# VISUR-N_a.net
KiCad netlist of a schematic drawn in Altium Designer
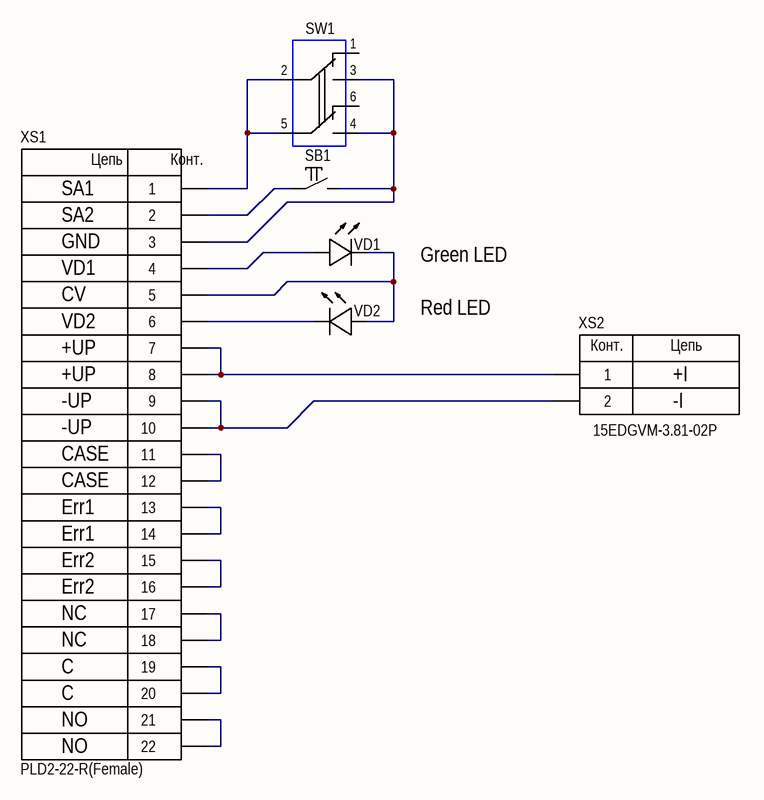
[diagram p0: VISUR-N_a.SchDoc]

(export (version "E")
  (design (tool "Eeschema 10.0.6"))
  (components
    (comp (ref "SB1")
      (value "~")
      (footprint "BUT: 6x6")
      (fields
        (field (name "MANUFACTURER") "TE Connectivity")
        (field (name "VALUEMANUFACTURERPARTNUMBER") "Tactile button, 6x6mm")
        (field (name "PARTNUMBER") "FSM2JSMAATR")
      )
      (libsource (lib "electromechanics") (part "Button_tactile"))
    )
    (comp (ref "SW1")
      (value "JS202011SCQN")
      (footprint "JS202011CQN")
      (description "Переключатель")
      (fields
        (field (name "MANUFACTURER") "C&K Component")
        (field (name "REPLACEMENTPART1PARTNUMBER") "is-1390")
      )
      (libsource (lib "Switch") (part "JS202011SCQN"))
    )
    (comp (ref "VD1")
      (value "KM2520SURCK09")
      (footprint "KM2520SURCK09")
      (description "LED")
      (libsource (lib "Kingbright LED") (part "KM2520SURCK09"))
    )
    (comp (ref "VD2")
      (value "KM2520SURCK09")
      (footprint "KM2520SURCK09")
      (description "LED")
      (libsource (lib "Kingbright LED") (part "KM2520SURCK09"))
    )
    (comp (ref "XS1")
      (value "PLD2-22-R(Female)")
      (footprint "CON: PLD2-22-R(Female)")
      (libsource (lib "connector") (part "PLD2-22(Female)"))
    )
    (comp (ref "XS2")
      (value "15EDGVM-3.81-02P")
      (footprint "CON: 15EDGVM-3.81-02P")
      (libsource (lib "connector") (part "15EDGVM-3.81-02P"))
    )
  )
  (nets
    (net (code "1") (name "Net-(SB1-Pad1)") (class "Default")
      (node (ref "SB1") (pin "1") (pinfunction "1_1") (pintype "passive"))
      (node (ref "XS1") (pin "2") (pinfunction "2_2") (pintype "passive"))
    )
    (net (code "2") (name "Net-(SB1-Pad2)") (class "Default")
      (node (ref "SB1") (pin "2") (pinfunction "2_2") (pintype "passive"))
      (node (ref "SW1") (pin "3") (pinfunction "3_3") (pintype "passive"))
      (node (ref "SW1") (pin "4") (pinfunction "4_4") (pintype "passive"))
      (node (ref "XS1") (pin "3") (pinfunction "3_3") (pintype "power_in"))
    )
    (net (code "3") (name "Net-(SW1-Pad2)") (class "Default")
      (node (ref "SW1") (pin "2") (pinfunction "2_2") (pintype "passive"))
      (node (ref "SW1") (pin "5") (pinfunction "5_5") (pintype "passive"))
      (node (ref "XS1") (pin "1") (pinfunction "1_1") (pintype "passive"))
    )
    (net (code "4") (name "Net-(VD1-A)") (class "Default")
      (node (ref "VD1") (pin "1") (pinfunction "A_1") (pintype "passive"))
      (node (ref "XS1") (pin "4") (pinfunction "4_4") (pintype "power_in"))
    )
    (net (code "5") (name "Net-(VD1-K)") (class "Default")
      (node (ref "VD1") (pin "2") (pinfunction "K_2") (pintype "passive"))
      (node (ref "VD2") (pin "1") (pinfunction "A_1") (pintype "passive"))
      (node (ref "XS1") (pin "5") (pinfunction "5_5") (pintype "power_in"))
    )
    (net (code "6") (name "Net-(VD2-K)") (class "Default")
      (node (ref "VD2") (pin "2") (pinfunction "K_2") (pintype "passive"))
      (node (ref "XS1") (pin "6") (pinfunction "6_6") (pintype "power_in"))
    )
    (net (code "7") (name "Net-(XS1-Pad7)") (class "Default")
      (node (ref "XS1") (pin "7") (pinfunction "7_7") (pintype "power_in"))
      (node (ref "XS1") (pin "8") (pinfunction "8_8") (pintype "power_in"))
      (node (ref "XS2") (pin "1") (pinfunction "1_1") (pintype "passive"))
    )
    (net (code "8") (name "Net-(XS1-Pad10)") (class "Default")
      (node (ref "XS1") (pin "10") (pinfunction "10_10") (pintype "power_in"))
      (node (ref "XS1") (pin "9") (pinfunction "9_9") (pintype "power_in"))
      (node (ref "XS2") (pin "2") (pinfunction "2_2") (pintype "passive"))
    )
    (net (code "9") (name "Net-(XS1-Pad11)") (class "Default")
      (node (ref "XS1") (pin "11") (pinfunction "11_11") (pintype "power_in"))
      (node (ref "XS1") (pin "12") (pinfunction "12_12") (pintype "power_in"))
    )
    (net (code "10") (name "Net-(XS1-Pad13)") (class "Default")
      (node (ref "XS1") (pin "13") (pinfunction "13_13") (pintype "power_in"))
      (node (ref "XS1") (pin "14") (pinfunction "14_14") (pintype "power_in"))
    )
    (net (code "11") (name "Net-(XS1-Pad15)") (class "Default")
      (node (ref "XS1") (pin "15") (pinfunction "15_15") (pintype "passive"))
      (node (ref "XS1") (pin "16") (pinfunction "16_16") (pintype "passive"))
    )
    (net (code "12") (name "Net-(XS1-Pad17)") (class "Default")
      (node (ref "XS1") (pin "17") (pinfunction "17_17") (pintype "passive"))
      (node (ref "XS1") (pin "18") (pinfunction "18_18") (pintype "passive"))
    )
    (net (code "13") (name "Net-(XS1-Pad19)") (class "Default")
      (node (ref "XS1") (pin "19") (pinfunction "19_19") (pintype "passive"))
      (node (ref "XS1") (pin "20") (pinfunction "20_20") (pintype "passive"))
    )
    (net (code "14") (name "Net-(XS1-Pad21)") (class "Default")
      (node (ref "XS1") (pin "21") (pinfunction "21_21") (pintype "passive"))
      (node (ref "XS1") (pin "22") (pinfunction "22_22") (pintype "passive"))
    )
    (net (code "15") (name "unconnected-(SW1-Pad1)") (class "Default")
      (node (ref "SW1") (pin "1") (pinfunction "1_1") (pintype "passive"))
    )
    (net (code "16") (name "unconnected-(SW1-Pad6)") (class "Default")
      (node (ref "SW1") (pin "6") (pinfunction "6_6") (pintype "passive"))
    )
  )
)
